# 5-PadsSeq.net
KiCad netlist of a schematic drawn in Altium Designer
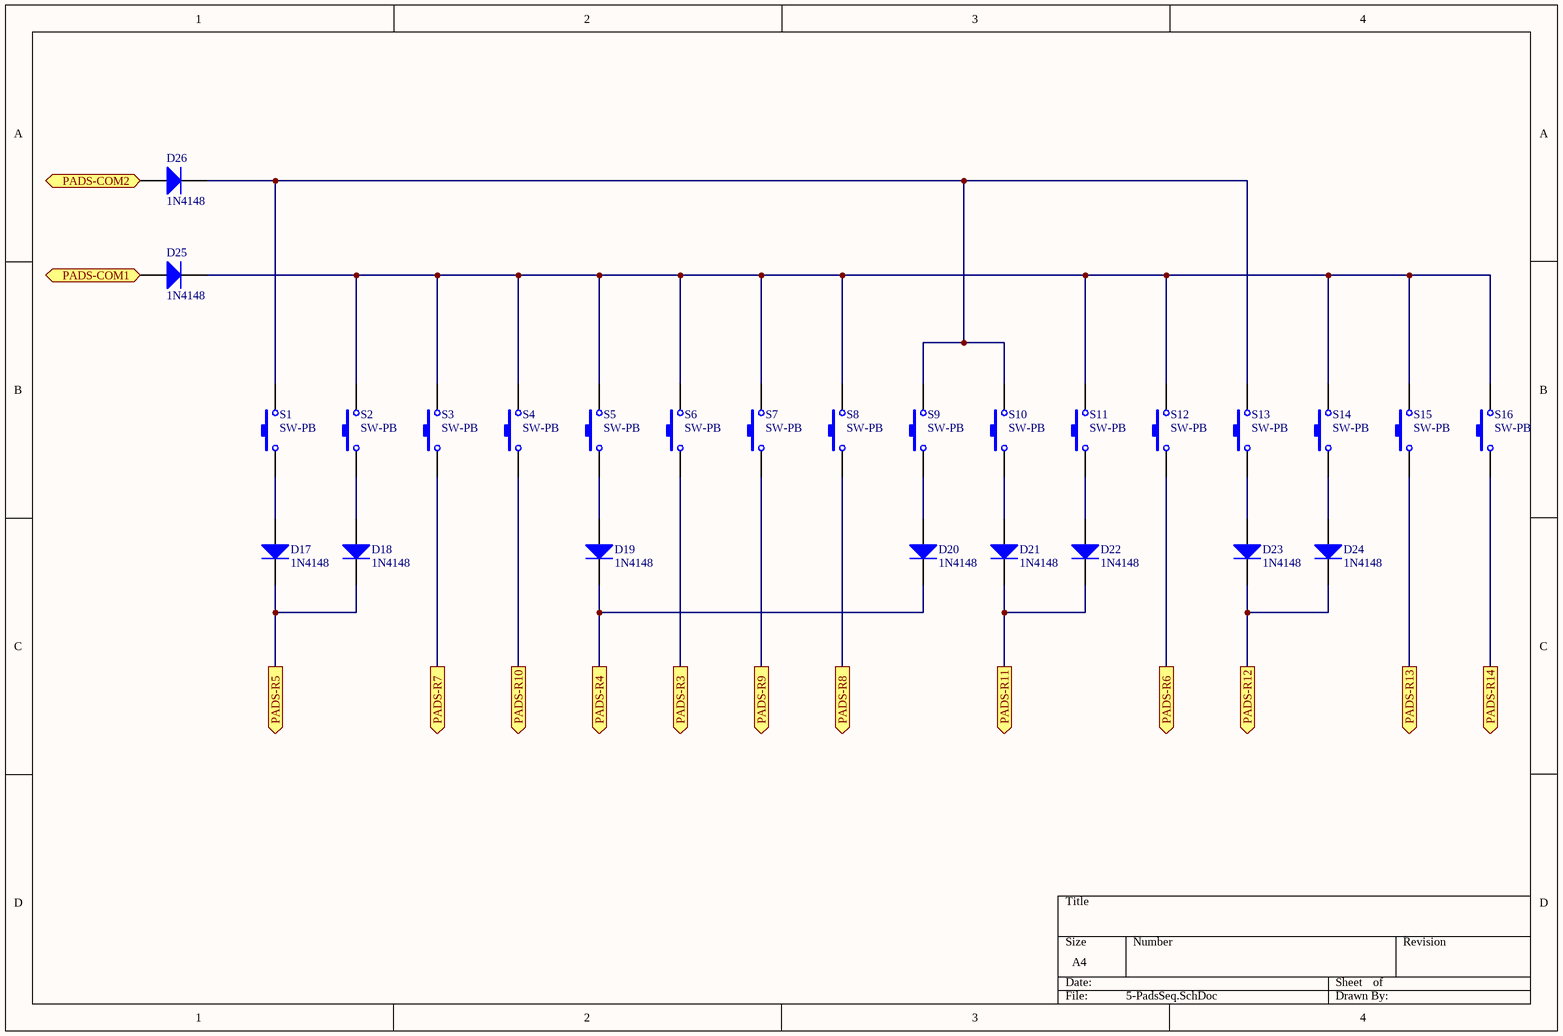
[diagram p0: 5-PadsSeq.SchDoc]

(export (version "E")
  (design (tool "Eeschema 10.0.6"))
  (components
    (comp (ref "D17")
      (value "1N4148")
      (footprint "SMC")
      (description "Default Diode")
      (fields (field (name "PUBLISHER") "Altium Limited"))
      (libsource (lib "Miscellaneous Devices") (part "Diode"))
    )
    (comp (ref "D18")
      (value "1N4148")
      (footprint "SMC")
      (description "Default Diode")
      (fields (field (name "PUBLISHER") "Altium Limited"))
      (libsource (lib "Miscellaneous Devices") (part "Diode"))
    )
    (comp (ref "D19")
      (value "1N4148")
      (footprint "SMC")
      (description "Default Diode")
      (fields (field (name "PUBLISHER") "Altium Limited"))
      (libsource (lib "Miscellaneous Devices") (part "Diode"))
    )
    (comp (ref "D20")
      (value "1N4148")
      (footprint "SMC")
      (description "Default Diode")
      (fields (field (name "PUBLISHER") "Altium Limited"))
      (libsource (lib "Miscellaneous Devices") (part "Diode"))
    )
    (comp (ref "D21")
      (value "1N4148")
      (footprint "SMC")
      (description "Default Diode")
      (fields (field (name "PUBLISHER") "Altium Limited"))
      (libsource (lib "Miscellaneous Devices") (part "Diode"))
    )
    (comp (ref "D22")
      (value "1N4148")
      (footprint "SMC")
      (description "Default Diode")
      (fields (field (name "PUBLISHER") "Altium Limited"))
      (libsource (lib "Miscellaneous Devices") (part "Diode"))
    )
    (comp (ref "D23")
      (value "1N4148")
      (footprint "SMC")
      (description "Default Diode")
      (fields (field (name "PUBLISHER") "Altium Limited"))
      (libsource (lib "Miscellaneous Devices") (part "Diode"))
    )
    (comp (ref "D24")
      (value "1N4148")
      (footprint "SMC")
      (description "Default Diode")
      (fields (field (name "PUBLISHER") "Altium Limited"))
      (libsource (lib "Miscellaneous Devices") (part "Diode"))
    )
    (comp (ref "D25")
      (value "1N4148")
      (footprint "SMC")
      (description "Default Diode")
      (fields (field (name "PUBLISHER") "Altium Limited"))
      (libsource (lib "Miscellaneous Devices") (part "Diode"))
    )
    (comp (ref "D26")
      (value "1N4148")
      (footprint "SMC")
      (description "Default Diode")
      (fields (field (name "PUBLISHER") "Altium Limited"))
      (libsource (lib "Miscellaneous Devices") (part "Diode"))
    )
    (comp (ref "S1")
      (value "SW-PB")
      (footprint "SPST-2")
      (description "Switch")
      (fields (field (name "PUBLISHER") "Altium Limited"))
      (libsource (lib "Miscellaneous Devices") (part "SW-PB"))
    )
    (comp (ref "S2")
      (value "SW-PB")
      (footprint "SPST-2")
      (description "Switch")
      (fields (field (name "PUBLISHER") "Altium Limited"))
      (libsource (lib "Miscellaneous Devices") (part "SW-PB"))
    )
    (comp (ref "S3")
      (value "SW-PB")
      (footprint "SPST-2")
      (description "Switch")
      (fields (field (name "PUBLISHER") "Altium Limited"))
      (libsource (lib "Miscellaneous Devices") (part "SW-PB"))
    )
    (comp (ref "S4")
      (value "SW-PB")
      (footprint "SPST-2")
      (description "Switch")
      (fields (field (name "PUBLISHER") "Altium Limited"))
      (libsource (lib "Miscellaneous Devices") (part "SW-PB"))
    )
    (comp (ref "S5")
      (value "SW-PB")
      (footprint "SPST-2")
      (description "Switch")
      (fields (field (name "PUBLISHER") "Altium Limited"))
      (libsource (lib "Miscellaneous Devices") (part "SW-PB"))
    )
    (comp (ref "S6")
      (value "SW-PB")
      (footprint "SPST-2")
      (description "Switch")
      (fields (field (name "PUBLISHER") "Altium Limited"))
      (libsource (lib "Miscellaneous Devices") (part "SW-PB"))
    )
    (comp (ref "S7")
      (value "SW-PB")
      (footprint "SPST-2")
      (description "Switch")
      (fields (field (name "PUBLISHER") "Altium Limited"))
      (libsource (lib "Miscellaneous Devices") (part "SW-PB"))
    )
    (comp (ref "S8")
      (value "SW-PB")
      (footprint "SPST-2")
      (description "Switch")
      (fields (field (name "PUBLISHER") "Altium Limited"))
      (libsource (lib "Miscellaneous Devices") (part "SW-PB"))
    )
    (comp (ref "S9")
      (value "SW-PB")
      (footprint "SPST-2")
      (description "Switch")
      (fields (field (name "PUBLISHER") "Altium Limited"))
      (libsource (lib "Miscellaneous Devices") (part "SW-PB"))
    )
    (comp (ref "S10")
      (value "SW-PB")
      (footprint "SPST-2")
      (description "Switch")
      (fields (field (name "PUBLISHER") "Altium Limited"))
      (libsource (lib "Miscellaneous Devices") (part "SW-PB"))
    )
    (comp (ref "S11")
      (value "SW-PB")
      (footprint "SPST-2")
      (description "Switch")
      (fields (field (name "PUBLISHER") "Altium Limited"))
      (libsource (lib "Miscellaneous Devices") (part "SW-PB"))
    )
    (comp (ref "S12")
      (value "SW-PB")
      (footprint "SPST-2")
      (description "Switch")
      (fields (field (name "PUBLISHER") "Altium Limited"))
      (libsource (lib "Miscellaneous Devices") (part "SW-PB"))
    )
    (comp (ref "S13")
      (value "SW-PB")
      (footprint "SPST-2")
      (description "Switch")
      (fields (field (name "PUBLISHER") "Altium Limited"))
      (libsource (lib "Miscellaneous Devices") (part "SW-PB"))
    )
    (comp (ref "S14")
      (value "SW-PB")
      (footprint "SPST-2")
      (description "Switch")
      (fields (field (name "PUBLISHER") "Altium Limited"))
      (libsource (lib "Miscellaneous Devices") (part "SW-PB"))
    )
    (comp (ref "S15")
      (value "SW-PB")
      (footprint "SPST-2")
      (description "Switch")
      (fields (field (name "PUBLISHER") "Altium Limited"))
      (libsource (lib "Miscellaneous Devices") (part "SW-PB"))
    )
    (comp (ref "S16")
      (value "SW-PB")
      (footprint "SPST-2")
      (description "Switch")
      (fields (field (name "PUBLISHER") "Altium Limited"))
      (libsource (lib "Miscellaneous Devices") (part "SW-PB"))
    )
  )
  (nets
    (net (code "1") (name "/PADS-COM1") (class "Default")
      (node (ref "D25") (pin "1") (pinfunction "A_1") (pintype "passive"))
    )
    (net (code "2") (name "/PADS-COM2") (class "Default")
      (node (ref "D26") (pin "1") (pinfunction "A_1") (pintype "passive"))
    )
    (net (code "3") (name "/PADS-R3") (class "Default")
      (node (ref "S6") (pin "1") (pinfunction "1_1") (pintype "passive"))
    )
    (net (code "4") (name "/PADS-R4") (class "Default")
      (node (ref "D19") (pin "2") (pinfunction "K_2") (pintype "passive"))
      (node (ref "D20") (pin "2") (pinfunction "K_2") (pintype "passive"))
    )
    (net (code "5") (name "/PADS-R5") (class "Default")
      (node (ref "D17") (pin "2") (pinfunction "K_2") (pintype "passive"))
      (node (ref "D18") (pin "2") (pinfunction "K_2") (pintype "passive"))
    )
    (net (code "6") (name "/PADS-R6") (class "Default")
      (node (ref "S12") (pin "1") (pinfunction "1_1") (pintype "passive"))
    )
    (net (code "7") (name "/PADS-R7") (class "Default")
      (node (ref "S3") (pin "1") (pinfunction "1_1") (pintype "passive"))
    )
    (net (code "8") (name "/PADS-R8") (class "Default")
      (node (ref "S8") (pin "1") (pinfunction "1_1") (pintype "passive"))
    )
    (net (code "9") (name "/PADS-R9") (class "Default")
      (node (ref "S7") (pin "1") (pinfunction "1_1") (pintype "passive"))
    )
    (net (code "10") (name "/PADS-R10") (class "Default")
      (node (ref "S4") (pin "1") (pinfunction "1_1") (pintype "passive"))
    )
    (net (code "11") (name "/PADS-R11") (class "Default")
      (node (ref "D21") (pin "2") (pinfunction "K_2") (pintype "passive"))
      (node (ref "D22") (pin "2") (pinfunction "K_2") (pintype "passive"))
    )
    (net (code "12") (name "/PADS-R12") (class "Default")
      (node (ref "D23") (pin "2") (pinfunction "K_2") (pintype "passive"))
      (node (ref "D24") (pin "2") (pinfunction "K_2") (pintype "passive"))
    )
    (net (code "13") (name "/PADS-R13") (class "Default")
      (node (ref "S15") (pin "1") (pinfunction "1_1") (pintype "passive"))
    )
    (net (code "14") (name "/PADS-R14") (class "Default")
      (node (ref "S16") (pin "1") (pinfunction "1_1") (pintype "passive"))
    )
    (net (code "15") (name "Net-(D17-A)") (class "Default")
      (node (ref "D17") (pin "1") (pinfunction "A_1") (pintype "passive"))
      (node (ref "S1") (pin "1") (pinfunction "1_1") (pintype "passive"))
    )
    (net (code "16") (name "Net-(D18-A)") (class "Default")
      (node (ref "D18") (pin "1") (pinfunction "A_1") (pintype "passive"))
      (node (ref "S2") (pin "1") (pinfunction "1_1") (pintype "passive"))
    )
    (net (code "17") (name "Net-(D19-A)") (class "Default")
      (node (ref "D19") (pin "1") (pinfunction "A_1") (pintype "passive"))
      (node (ref "S5") (pin "1") (pinfunction "1_1") (pintype "passive"))
    )
    (net (code "18") (name "Net-(D20-A)") (class "Default")
      (node (ref "D20") (pin "1") (pinfunction "A_1") (pintype "passive"))
      (node (ref "S9") (pin "1") (pinfunction "1_1") (pintype "passive"))
    )
    (net (code "19") (name "Net-(D21-A)") (class "Default")
      (node (ref "D21") (pin "1") (pinfunction "A_1") (pintype "passive"))
      (node (ref "S10") (pin "1") (pinfunction "1_1") (pintype "passive"))
    )
    (net (code "20") (name "Net-(D22-A)") (class "Default")
      (node (ref "D22") (pin "1") (pinfunction "A_1") (pintype "passive"))
      (node (ref "S11") (pin "1") (pinfunction "1_1") (pintype "passive"))
    )
    (net (code "21") (name "Net-(D23-A)") (class "Default")
      (node (ref "D23") (pin "1") (pinfunction "A_1") (pintype "passive"))
      (node (ref "S13") (pin "1") (pinfunction "1_1") (pintype "passive"))
    )
    (net (code "22") (name "Net-(D24-A)") (class "Default")
      (node (ref "D24") (pin "1") (pinfunction "A_1") (pintype "passive"))
      (node (ref "S14") (pin "1") (pinfunction "1_1") (pintype "passive"))
    )
    (net (code "23") (name "Net-(D25-K)") (class "Default")
      (node (ref "D25") (pin "2") (pinfunction "K_2") (pintype "passive"))
      (node (ref "S11") (pin "2") (pinfunction "2_2") (pintype "passive"))
      (node (ref "S12") (pin "2") (pinfunction "2_2") (pintype "passive"))
      (node (ref "S14") (pin "2") (pinfunction "2_2") (pintype "passive"))
      (node (ref "S15") (pin "2") (pinfunction "2_2") (pintype "passive"))
      (node (ref "S16") (pin "2") (pinfunction "2_2") (pintype "passive"))
      (node (ref "S2") (pin "2") (pinfunction "2_2") (pintype "passive"))
      (node (ref "S3") (pin "2") (pinfunction "2_2") (pintype "passive"))
      (node (ref "S4") (pin "2") (pinfunction "2_2") (pintype "passive"))
      (node (ref "S5") (pin "2") (pinfunction "2_2") (pintype "passive"))
      (node (ref "S6") (pin "2") (pinfunction "2_2") (pintype "passive"))
      (node (ref "S7") (pin "2") (pinfunction "2_2") (pintype "passive"))
      (node (ref "S8") (pin "2") (pinfunction "2_2") (pintype "passive"))
    )
    (net (code "24") (name "Net-(D26-K)") (class "Default")
      (node (ref "D26") (pin "2") (pinfunction "K_2") (pintype "passive"))
      (node (ref "S1") (pin "2") (pinfunction "2_2") (pintype "passive"))
      (node (ref "S10") (pin "2") (pinfunction "2_2") (pintype "passive"))
      (node (ref "S13") (pin "2") (pinfunction "2_2") (pintype "passive"))
      (node (ref "S9") (pin "2") (pinfunction "2_2") (pintype "passive"))
    )
  )
)
